# table2.net
KiCad netlist of a schematic drawn in EasyEDA
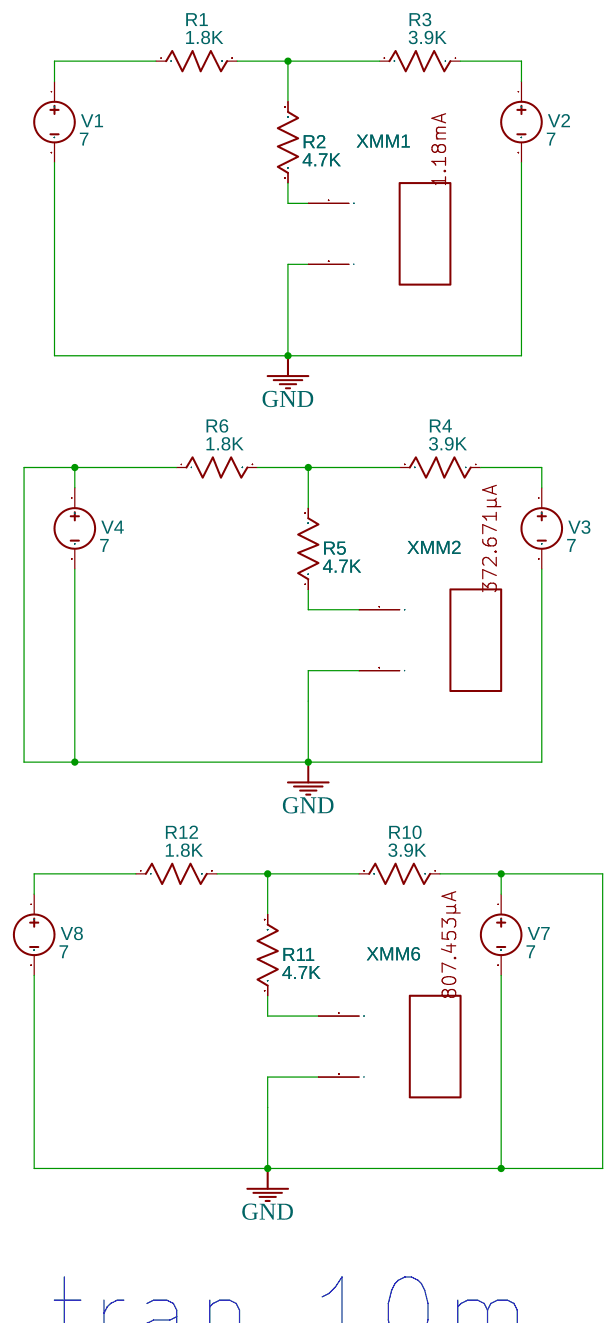
[diagram p0: schematic sheet]

(export (version "E")
  (design (tool "Eeschema 10.0.6"))
  (components
    (comp (ref "R1") (value "1.8K") (libsource (lib "") (part "Resistor_US_2")))
    (comp (ref "R2") (value "4.7K") (libsource (lib "") (part "Resistor_US")))
    (comp (ref "R3") (value "3.9K") (libsource (lib "") (part "Resistor_US_1")))
    (comp (ref "R4") (value "3.9K") (libsource (lib "") (part "Resistor_US_1")))
    (comp (ref "R5") (value "4.7K") (libsource (lib "") (part "Resistor_US")))
    (comp (ref "R6") (value "1.8K") (libsource (lib "") (part "Resistor_US_2")))
    (comp (ref "R10") (value "3.9K") (libsource (lib "") (part "Resistor_US_1")))
    (comp (ref "R11") (value "4.7K") (libsource (lib "") (part "Resistor_US")))
    (comp (ref "R12") (value "1.8K") (libsource (lib "") (part "Resistor_US_2")))
    (comp (ref "V1") (value "7") (libsource (lib "") (part "VDC")))
    (comp (ref "V2") (value "7") (libsource (lib "") (part "VDC")))
    (comp (ref "V3") (value "7") (libsource (lib "") (part "VDC")))
    (comp (ref "V4") (value "7") (libsource (lib "") (part "VDC")))
    (comp (ref "V7") (value "7") (libsource (lib "") (part "VDC")))
    (comp (ref "V8") (value "7") (libsource (lib "") (part "VDC")))
    (comp (ref "XMM1") (value "Multimeter") (libsource (lib "") (part "MULTIMETER_2")))
    (comp (ref "XMM2") (value "Multimeter") (libsource (lib "") (part "MULTIMETER_1")))
    (comp (ref "XMM6") (value "Multimeter") (libsource (lib "") (part "MULTIMETER")))
  )
  (nets
    (net (code "1") (name "GND") (class "Default")
      (node (ref "R10") (pin "1") (pinfunction "1_1") (pintype "unspecified"))
      (node (ref "R6") (pin "1") (pinfunction "1_1") (pintype "unspecified"))
      (node (ref "V1") (pin "2") (pinfunction "2_2") (pintype "unspecified"))
      (node (ref "V2") (pin "2") (pinfunction "2_2") (pintype "unspecified"))
      (node (ref "V3") (pin "2") (pinfunction "2_2") (pintype "unspecified"))
      (node (ref "V4") (pin "1") (pinfunction "1_1") (pintype "unspecified"))
      (node (ref "V4") (pin "2") (pinfunction "2_2") (pintype "unspecified"))
      (node (ref "V7") (pin "1") (pinfunction "1_1") (pintype "unspecified"))
      (node (ref "V7") (pin "2") (pinfunction "2_2") (pintype "unspecified"))
      (node (ref "V8") (pin "2") (pinfunction "2_2") (pintype "unspecified"))
      (node (ref "XMM1") (pin "2") (pinfunction "I_2") (pintype "unspecified"))
      (node (ref "XMM2") (pin "2") (pinfunction "I_2") (pintype "unspecified"))
      (node (ref "XMM6") (pin "2") (pinfunction "I_2") (pintype "unspecified"))
    )
    (net (code "2") (name "Net-(R1-Pad1)") (class "Default")
      (node (ref "R1") (pin "1") (pinfunction "1_1") (pintype "unspecified"))
      (node (ref "V1") (pin "1") (pinfunction "1_1") (pintype "unspecified"))
    )
    (net (code "3") (name "Net-(R1-Pad2)") (class "Default")
      (node (ref "R1") (pin "2") (pinfunction "2_2") (pintype "unspecified"))
      (node (ref "R2") (pin "2") (pinfunction "2_2") (pintype "unspecified"))
      (node (ref "R3") (pin "2") (pinfunction "2_2") (pintype "unspecified"))
    )
    (net (code "4") (name "Net-(R3-Pad1)") (class "Default")
      (node (ref "R3") (pin "1") (pinfunction "1_1") (pintype "unspecified"))
      (node (ref "V2") (pin "1") (pinfunction "1_1") (pintype "unspecified"))
    )
    (net (code "5") (name "Net-(R4-Pad1)") (class "Default")
      (node (ref "R4") (pin "1") (pinfunction "1_1") (pintype "unspecified"))
      (node (ref "V3") (pin "1") (pinfunction "1_1") (pintype "unspecified"))
    )
    (net (code "6") (name "Net-(R4-Pad2)") (class "Default")
      (node (ref "R4") (pin "2") (pinfunction "2_2") (pintype "unspecified"))
      (node (ref "R5") (pin "2") (pinfunction "2_2") (pintype "unspecified"))
      (node (ref "R6") (pin "2") (pinfunction "2_2") (pintype "unspecified"))
    )
    (net (code "7") (name "Net-(R10-Pad2)") (class "Default")
      (node (ref "R10") (pin "2") (pinfunction "2_2") (pintype "unspecified"))
      (node (ref "R11") (pin "2") (pinfunction "2_2") (pintype "unspecified"))
      (node (ref "R12") (pin "2") (pinfunction "2_2") (pintype "unspecified"))
    )
    (net (code "8") (name "Net-(R12-Pad1)") (class "Default")
      (node (ref "R12") (pin "1") (pinfunction "1_1") (pintype "unspecified"))
      (node (ref "V8") (pin "1") (pinfunction "1_1") (pintype "unspecified"))
    )
    (net (code "9") (name "Net-(XMM1-+)") (class "Default")
      (node (ref "R2") (pin "1") (pinfunction "1_1") (pintype "unspecified"))
      (node (ref "XMM1") (pin "1") (pinfunction "+_1") (pintype "unspecified"))
    )
    (net (code "10") (name "Net-(XMM2-+)") (class "Default")
      (node (ref "R5") (pin "1") (pinfunction "1_1") (pintype "unspecified"))
      (node (ref "XMM2") (pin "1") (pinfunction "+_1") (pintype "unspecified"))
    )
    (net (code "11") (name "Net-(XMM6-+)") (class "Default")
      (node (ref "R11") (pin "1") (pinfunction "1_1") (pintype "unspecified"))
      (node (ref "XMM6") (pin "1") (pinfunction "+_1") (pintype "unspecified"))
    )
  )
)
